# UMR2_CS01_r2_TPL.net
KiCad netlist of a schematic drawn in EAGLE
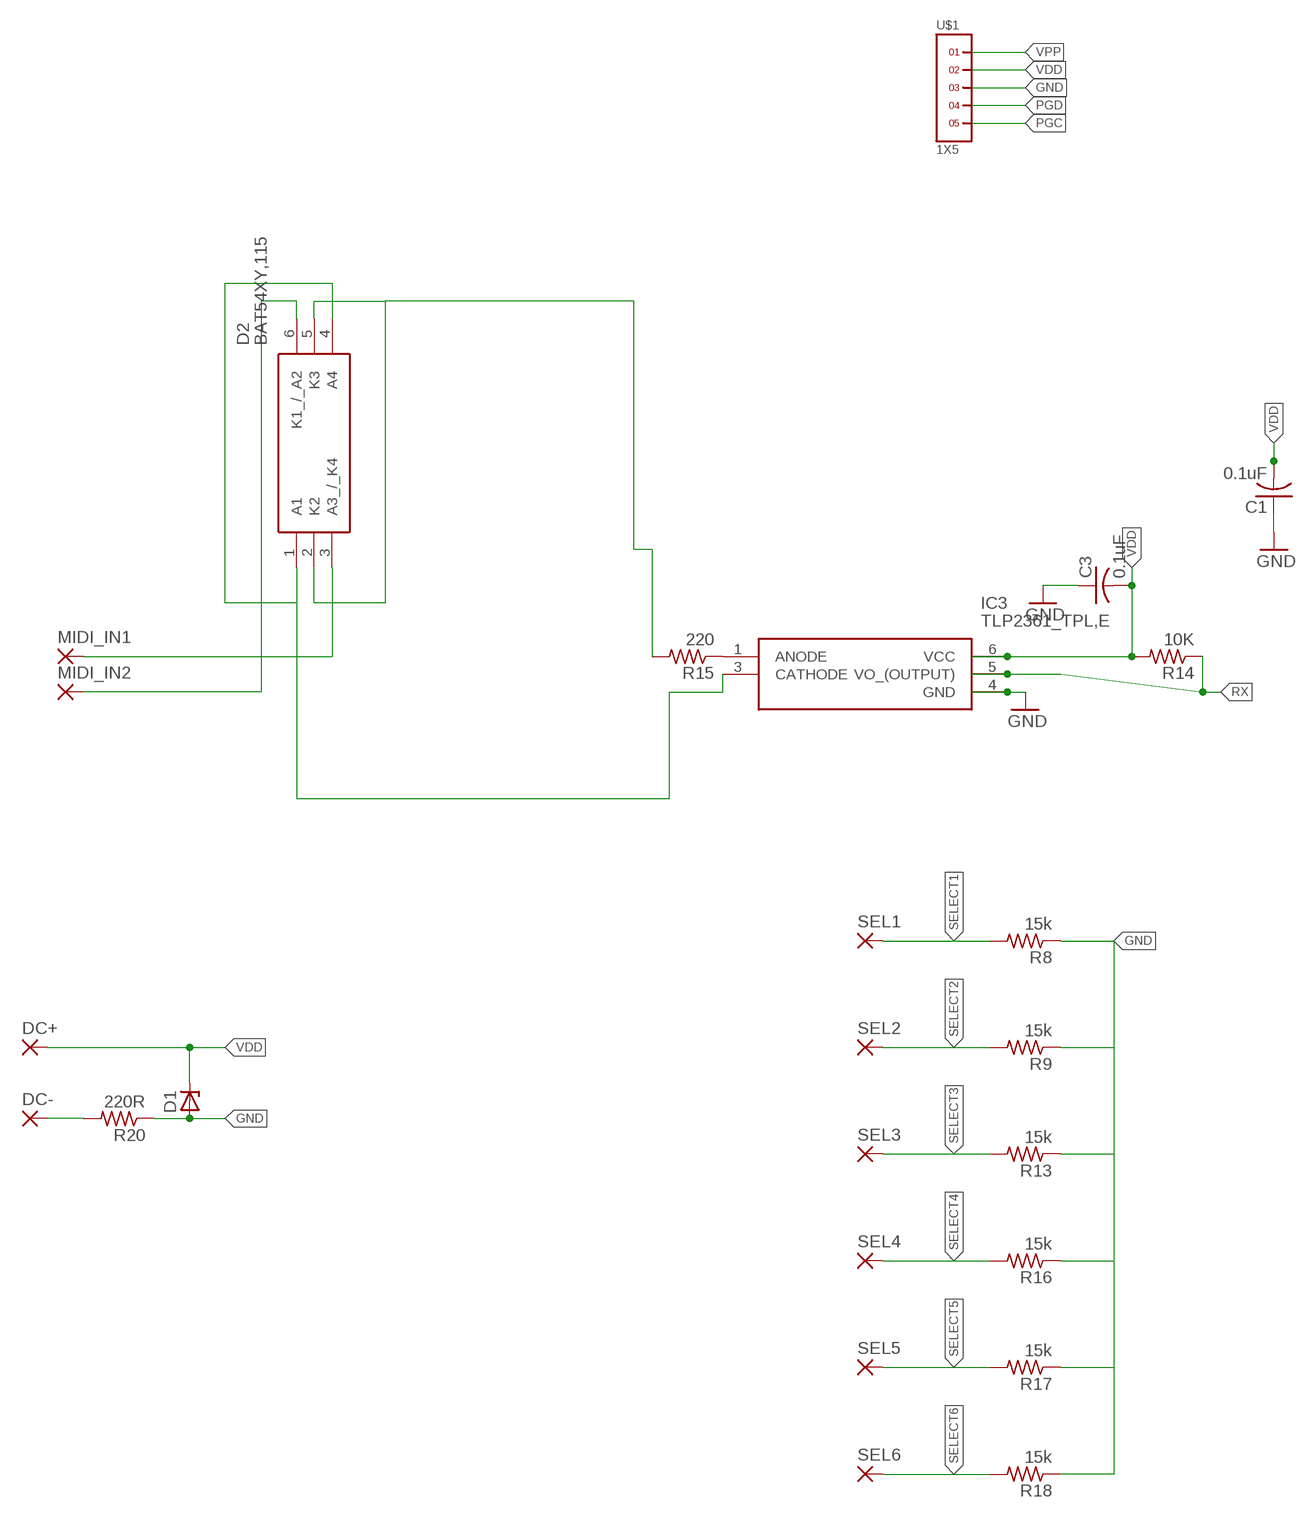
[diagram p0: schematic, sheet 1, part 1 of 2]
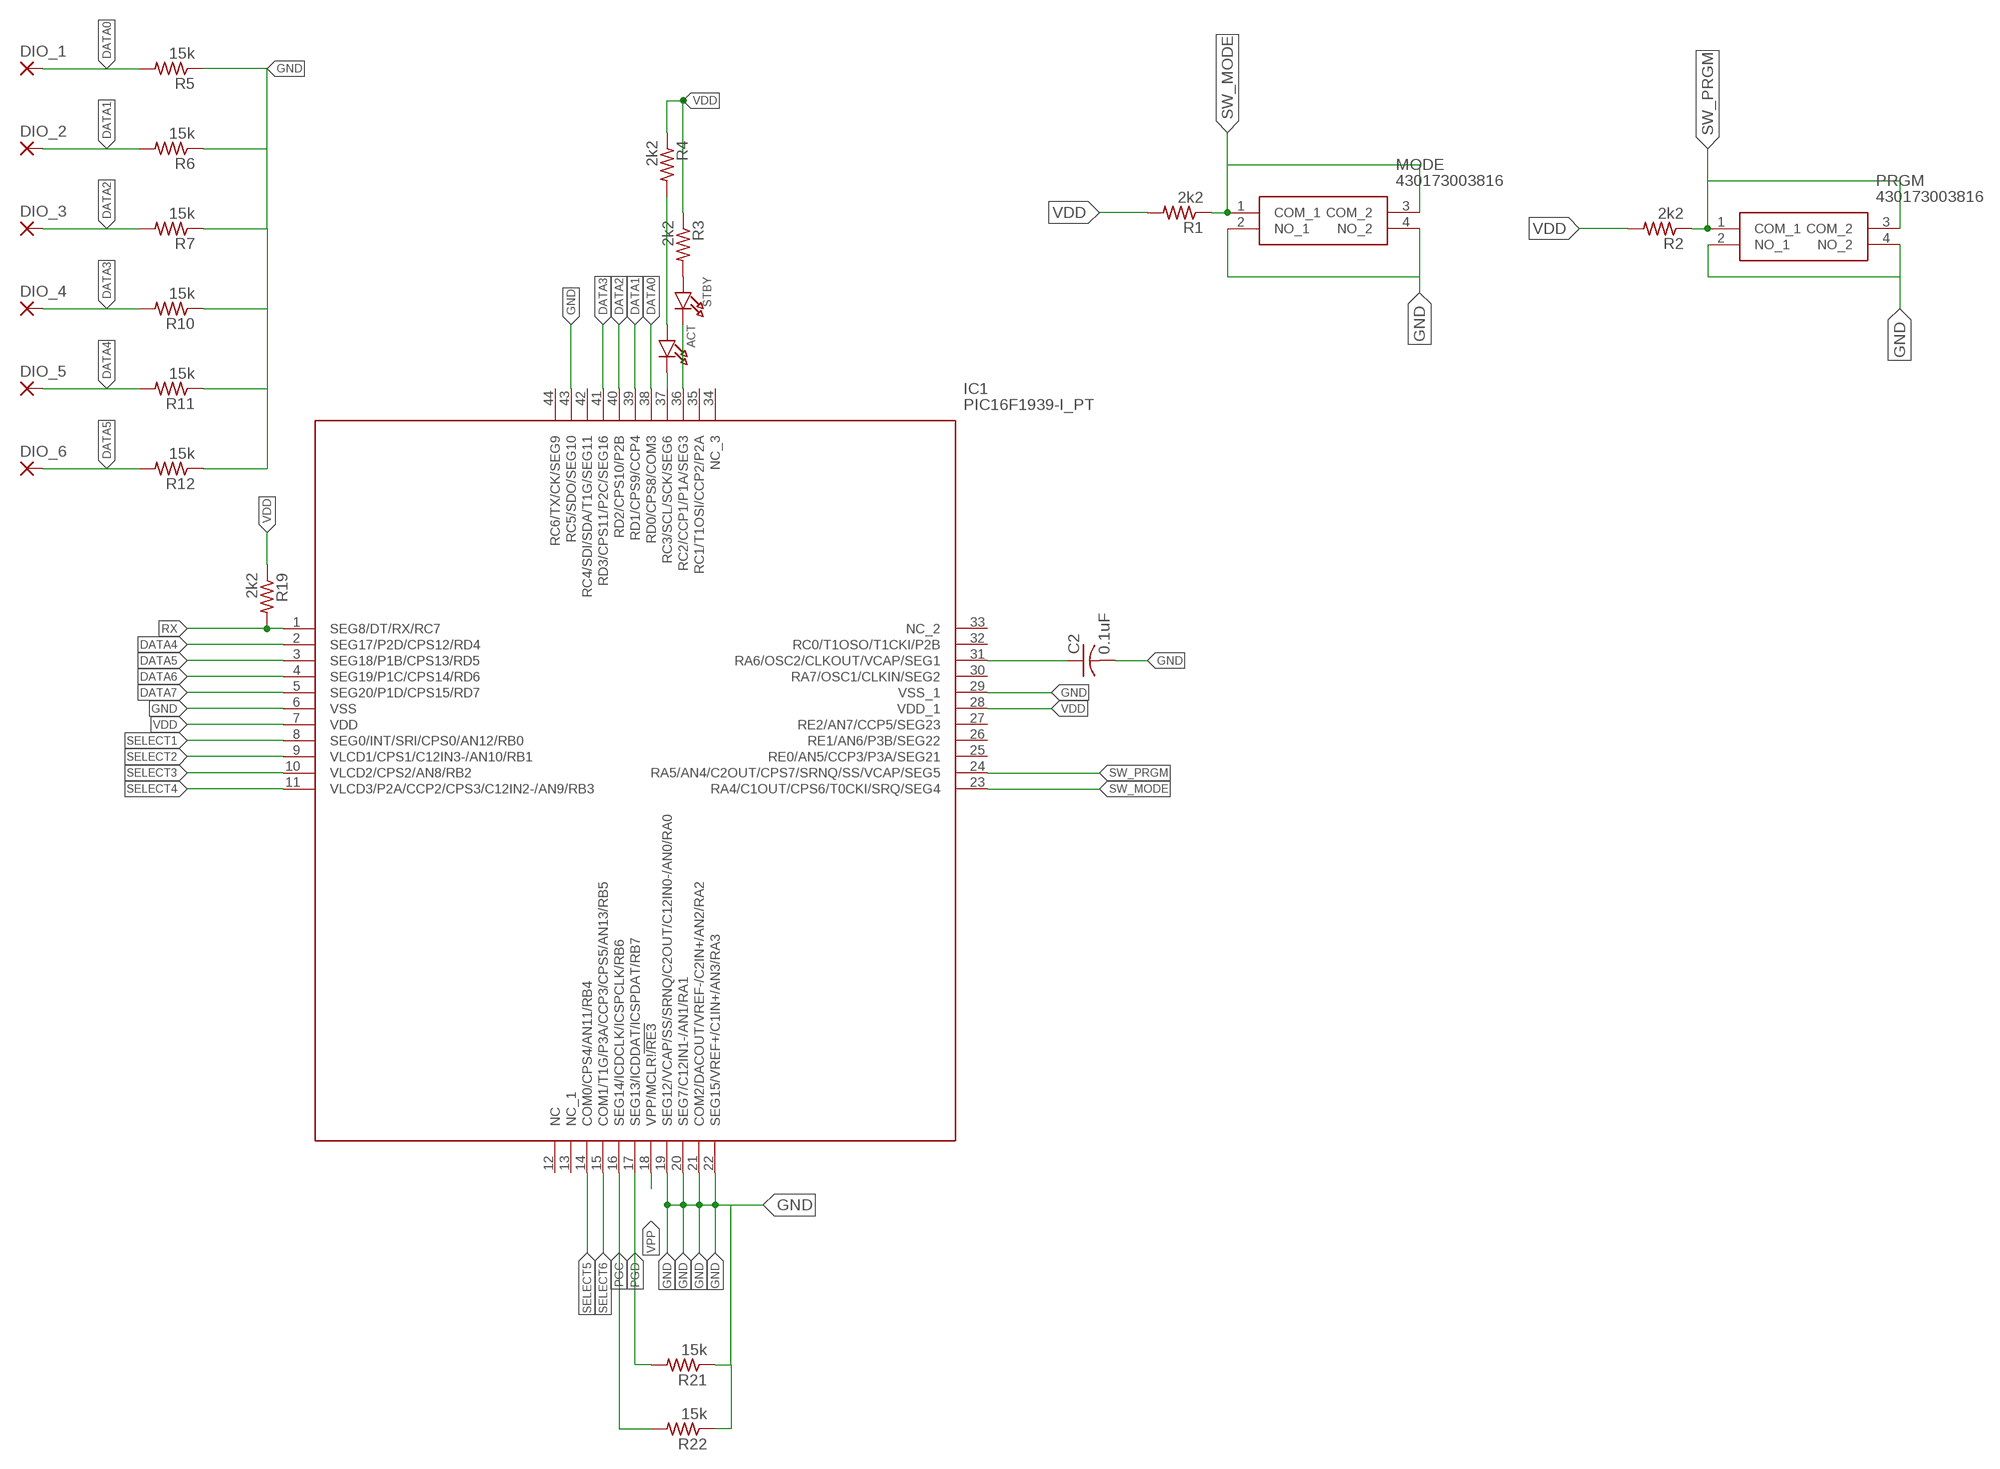
[diagram p1: schematic, sheet 1, part 2 of 2]

(export (version "E")
  (design (tool "Eeschema 10.0.6"))
  (components
    (comp (ref "ACT")
      (value "LED0603_NOOUTLINE")
      (footprint "eagle-import:CHIPLED_0603_NOOUTLINE")
      (libsource (lib "eagle-import") (part "LED0603_NOOUTLINE"))
    )
    (comp (ref "C1")
      (value "0.1uF")
      (footprint "eagle-import:RCL_C0603")
      (libsource (lib "eagle-import") (part "RCL_C-USC0603"))
    )
    (comp (ref "C2")
      (value "0.1uF")
      (footprint "eagle-import:RCL_C0603")
      (libsource (lib "eagle-import") (part "RCL_C-USC0603"))
    )
    (comp (ref "C3")
      (value "0.1uF")
      (footprint "eagle-import:RCL_C0603")
      (libsource (lib "eagle-import") (part "RCL_C-USC0603"))
    )
    (comp (ref "D1")
      (value "ZENER_DIODESOD123")
      (footprint "eagle-import:SOD123")
      (libsource (lib "eagle-import") (part "ZENER_DIODESOD123"))
    )
    (comp (ref "D2")
      (value "BAT54XY,115")
      (footprint "eagle-import:SOT65P210X110-6N")
      (fields (field (name "MOUSER_PART_NUMBER") "771-BAT54XY-T/R"))
      (libsource (lib "eagle-import") (part "BAT54XY,115"))
    )
    (comp (ref "DC+")
      (value "SMD2")
      (footprint "eagle-import:SMD1,27-2,54")
      (libsource (lib "eagle-import") (part "SMD2"))
    )
    (comp (ref "DC-")
      (value "SMD2")
      (footprint "eagle-import:SMD1,27-2,54")
      (libsource (lib "eagle-import") (part "SMD2"))
    )
    (comp (ref "DIO_1")
      (value "SMD2")
      (footprint "eagle-import:SMD1,27-2,54")
      (libsource (lib "eagle-import") (part "SMD2"))
    )
    (comp (ref "DIO_2")
      (value "SMD2")
      (footprint "eagle-import:SMD1,27-2,54")
      (libsource (lib "eagle-import") (part "SMD2"))
    )
    (comp (ref "DIO_3")
      (value "SMD2")
      (footprint "eagle-import:SMD1,27-2,54")
      (libsource (lib "eagle-import") (part "SMD2"))
    )
    (comp (ref "DIO_4")
      (value "SMD2")
      (footprint "eagle-import:SMD1,27-2,54")
      (libsource (lib "eagle-import") (part "SMD2"))
    )
    (comp (ref "DIO_5")
      (value "SMD2")
      (footprint "eagle-import:SMD1,27-2,54")
      (libsource (lib "eagle-import") (part "SMD2"))
    )
    (comp (ref "DIO_6")
      (value "SMD2")
      (footprint "eagle-import:SMD1,27-2,54")
      (libsource (lib "eagle-import") (part "SMD2"))
    )
    (comp (ref "IC1")
      (value "PIC16F1939-I_PT")
      (footprint "eagle-import:QFP80P1200X1200X120-44N")
      (fields
        (field (name "MANUFACTURER_PART_NUMBER") "PIC16F1939-I/PT")
        (field (name "MOUSER_PART_NUMBER") "579-PIC16F1939-I/PT")
      )
      (libsource (lib "eagle-import") (part "PIC16F1939-I_PT"))
    )
    (comp (ref "IC3")
      (value "TLP2361_TPL,E")
      (footprint "eagle-import:11-4L1S(5-PIN-SOIC)")
      (fields
        (field (name "MANUFACTURER_PART_NUMBER") "TLP2361(TPL,E")
        (field (name "MOUSER_PART_NUMBER") "757-TLP2361(TPLE")
      )
      (libsource (lib "eagle-import") (part "TLP2361_TPL,E"))
    )
    (comp (ref "MIDI_IN1")
      (value "SMD2")
      (footprint "eagle-import:SMD1,27-2,54")
      (libsource (lib "eagle-import") (part "SMD2"))
    )
    (comp (ref "MIDI_IN2")
      (value "SMD2")
      (footprint "eagle-import:SMD1,27-2,54")
      (libsource (lib "eagle-import") (part "SMD2"))
    )
    (comp (ref "MODE")
      (value "430173003816")
      (footprint "eagle-import:430173003816")
      (fields (field (name "MOUSER_PART_NUMBER") "710-430173003816"))
      (libsource (lib "eagle-import") (part "430173003816"))
    )
    (comp (ref "PRGM")
      (value "430173003816")
      (footprint "eagle-import:430173003816")
      (fields (field (name "MOUSER_PART_NUMBER") "710-430173003816"))
      (libsource (lib "eagle-import") (part "430173003816"))
    )
    (comp (ref "R1")
      (value "2k2")
      (footprint "eagle-import:RCL_R0603")
      (libsource (lib "eagle-import") (part "RCL_R-US_R0603"))
    )
    (comp (ref "R2")
      (value "2k2")
      (footprint "eagle-import:RCL_R0603")
      (libsource (lib "eagle-import") (part "RCL_R-US_R0603"))
    )
    (comp (ref "R3")
      (value "2k2")
      (footprint "eagle-import:RCL_R0603")
      (libsource (lib "eagle-import") (part "RCL_R-US_R0603"))
    )
    (comp (ref "R4")
      (value "2k2")
      (footprint "eagle-import:RCL_R0603")
      (libsource (lib "eagle-import") (part "RCL_R-US_R0603"))
    )
    (comp (ref "R5")
      (value "15k")
      (footprint "eagle-import:RCL_R0603")
      (libsource (lib "eagle-import") (part "RCL_R-US_R0603"))
    )
    (comp (ref "R6")
      (value "15k")
      (footprint "eagle-import:RCL_R0603")
      (libsource (lib "eagle-import") (part "RCL_R-US_R0603"))
    )
    (comp (ref "R7")
      (value "15k")
      (footprint "eagle-import:RCL_R0603")
      (libsource (lib "eagle-import") (part "RCL_R-US_R0603"))
    )
    (comp (ref "R8")
      (value "15k")
      (footprint "eagle-import:RCL_R0603")
      (libsource (lib "eagle-import") (part "RCL_R-US_R0603"))
    )
    (comp (ref "R9")
      (value "15k")
      (footprint "eagle-import:RCL_R0603")
      (libsource (lib "eagle-import") (part "RCL_R-US_R0603"))
    )
    (comp (ref "R10")
      (value "15k")
      (footprint "eagle-import:RCL_R0603")
      (libsource (lib "eagle-import") (part "RCL_R-US_R0603"))
    )
    (comp (ref "R11")
      (value "15k")
      (footprint "eagle-import:RCL_R0603")
      (libsource (lib "eagle-import") (part "RCL_R-US_R0603"))
    )
    (comp (ref "R12")
      (value "15k")
      (footprint "eagle-import:RCL_R0603")
      (libsource (lib "eagle-import") (part "RCL_R-US_R0603"))
    )
    (comp (ref "R13")
      (value "15k")
      (footprint "eagle-import:RCL_R0603")
      (libsource (lib "eagle-import") (part "RCL_R-US_R0603"))
    )
    (comp (ref "R14")
      (value "10K")
      (footprint "eagle-import:RCL_R0603")
      (libsource (lib "eagle-import") (part "RCL_R-US_R0603"))
    )
    (comp (ref "R15")
      (value "220")
      (footprint "eagle-import:RCL_R0603")
      (libsource (lib "eagle-import") (part "RCL_R-US_R0603"))
    )
    (comp (ref "R16")
      (value "15k")
      (footprint "eagle-import:RCL_R0603")
      (libsource (lib "eagle-import") (part "RCL_R-US_R0603"))
    )
    (comp (ref "R17")
      (value "15k")
      (footprint "eagle-import:RCL_R0603")
      (libsource (lib "eagle-import") (part "RCL_R-US_R0603"))
    )
    (comp (ref "R18")
      (value "15k")
      (footprint "eagle-import:RCL_R0603")
      (libsource (lib "eagle-import") (part "RCL_R-US_R0603"))
    )
    (comp (ref "R19")
      (value "2k2")
      (footprint "eagle-import:RCL_R0603")
      (libsource (lib "eagle-import") (part "RCL_R-US_R0603"))
    )
    (comp (ref "R20")
      (value "220R")
      (footprint "eagle-import:RCL_R0603")
      (libsource (lib "eagle-import") (part "RCL_R-US_R0603"))
    )
    (comp (ref "R21")
      (value "15k")
      (footprint "eagle-import:RCL_R0603")
      (libsource (lib "eagle-import") (part "RCL_R-US_R0603"))
    )
    (comp (ref "R22")
      (value "15k")
      (footprint "eagle-import:RCL_R0603")
      (libsource (lib "eagle-import") (part "RCL_R-US_R0603"))
    )
    (comp (ref "SEL1")
      (value "SMD2")
      (footprint "eagle-import:SMD1,27-2,54")
      (libsource (lib "eagle-import") (part "SMD2"))
    )
    (comp (ref "SEL2")
      (value "SMD2")
      (footprint "eagle-import:SMD1,27-2,54")
      (libsource (lib "eagle-import") (part "SMD2"))
    )
    (comp (ref "SEL3")
      (value "SMD2")
      (footprint "eagle-import:SMD1,27-2,54")
      (libsource (lib "eagle-import") (part "SMD2"))
    )
    (comp (ref "SEL4")
      (value "SMD2")
      (footprint "eagle-import:SMD1,27-2,54")
      (libsource (lib "eagle-import") (part "SMD2"))
    )
    (comp (ref "SEL5")
      (value "SMD2")
      (footprint "eagle-import:SMD1,27-2,54")
      (libsource (lib "eagle-import") (part "SMD2"))
    )
    (comp (ref "SEL6")
      (value "SMD2")
      (footprint "eagle-import:SMD1,27-2,54")
      (libsource (lib "eagle-import") (part "SMD2"))
    )
    (comp (ref "STBY")
      (value "LED0603_NOOUTLINE")
      (footprint "eagle-import:CHIPLED_0603_NOOUTLINE")
      (libsource (lib "eagle-import") (part "LED0603_NOOUTLINE"))
    )
    (comp (ref "U$1")
      (value "1X5")
      (footprint "eagle-import:1X5")
      (libsource (lib "eagle-import") (part "1X5"))
    )
  )
  (nets
    (net (code "1") (name "DATA0") (class "Default")
      (node (ref "DIO_1") (pin "1") (pinfunction "P_1") (pintype "passive"))
      (node (ref "IC1") (pin "38") (pinfunction "RD0/CPS8/COM3_38") (pintype "bidirectional"))
      (node (ref "R5") (pin "2") (pinfunction "2_2") (pintype "passive"))
    )
    (net (code "2") (name "DATA1") (class "Default")
      (node (ref "DIO_2") (pin "1") (pinfunction "P_1") (pintype "passive"))
      (node (ref "IC1") (pin "39") (pinfunction "RD1/CPS9/CCP4_39") (pintype "bidirectional"))
      (node (ref "R6") (pin "2") (pinfunction "2_2") (pintype "passive"))
    )
    (net (code "3") (name "DATA2") (class "Default")
      (node (ref "DIO_3") (pin "1") (pinfunction "P_1") (pintype "passive"))
      (node (ref "IC1") (pin "40") (pinfunction "RD2/CPS10/P2B_40") (pintype "bidirectional"))
      (node (ref "R7") (pin "2") (pinfunction "2_2") (pintype "passive"))
    )
    (net (code "4") (name "DATA3") (class "Default")
      (node (ref "DIO_4") (pin "1") (pinfunction "P_1") (pintype "passive"))
      (node (ref "IC1") (pin "41") (pinfunction "RD3/CPS11/P2C/SEG16_41") (pintype "bidirectional"))
      (node (ref "R10") (pin "2") (pinfunction "2_2") (pintype "passive"))
    )
    (net (code "5") (name "DATA4") (class "Default")
      (node (ref "DIO_5") (pin "1") (pinfunction "P_1") (pintype "passive"))
      (node (ref "IC1") (pin "2") (pinfunction "SEG17/P2D/CPS12/RD4_2") (pintype "bidirectional"))
      (node (ref "R11") (pin "2") (pinfunction "2_2") (pintype "passive"))
    )
    (net (code "6") (name "DATA5") (class "Default")
      (node (ref "DIO_6") (pin "1") (pinfunction "P_1") (pintype "passive"))
      (node (ref "IC1") (pin "3") (pinfunction "SEG18/P1B/CPS13/RD5_3") (pintype "bidirectional"))
      (node (ref "R12") (pin "2") (pinfunction "2_2") (pintype "passive"))
    )
    (net (code "7") (name "DATA6") (class "Default")
      (node (ref "IC1") (pin "4") (pinfunction "SEG19/P1C/CPS14/RD6_4") (pintype "bidirectional"))
    )
    (net (code "8") (name "DATA7") (class "Default")
      (node (ref "IC1") (pin "5") (pinfunction "SEG20/P1D/CPS15/RD7_5") (pintype "bidirectional"))
    )
    (net (code "9") (name "GND") (class "Default")
      (node (ref "C1") (pin "1") (pinfunction "1_1") (pintype "passive"))
      (node (ref "C2") (pin "2") (pinfunction "2_2") (pintype "passive"))
      (node (ref "C3") (pin "1") (pinfunction "1_1") (pintype "passive"))
      (node (ref "D1") (pin "ANODE") (pinfunction "ANODE_ANODE") (pintype "passive"))
      (node (ref "IC1") (pin "19") (pinfunction "SEG12/VCAP/SS/SRNQ/C2OUT/C12IN0-/AN0/RA0_19") (pintype "output"))
      (node (ref "IC1") (pin "20") (pinfunction "SEG7/C12IN1-/AN1/RA1_20") (pintype "input"))
      (node (ref "IC1") (pin "21") (pinfunction "COM2/DACOUT/VREF-/C2IN+/AN2/RA2_21") (pintype "output"))
      (node (ref "IC1") (pin "22") (pinfunction "SEG15/VREF+/C1IN+/AN3/RA3_22") (pintype "input"))
      (node (ref "IC1") (pin "29") (pinfunction "VSS_1_29") (pintype "power_in"))
      (node (ref "IC1") (pin "43") (pinfunction "RC5/SDO/SEG10_43") (pintype "bidirectional"))
      (node (ref "IC1") (pin "6") (pinfunction "VSS_6") (pintype "power_in"))
      (node (ref "IC3") (pin "4") (pinfunction "GND_4") (pintype "bidirectional"))
      (node (ref "MODE") (pin "2") (pinfunction "NO_1_2") (pintype "bidirectional"))
      (node (ref "MODE") (pin "4") (pinfunction "NO_2_4") (pintype "bidirectional"))
      (node (ref "PRGM") (pin "2") (pinfunction "NO_1_2") (pintype "bidirectional"))
      (node (ref "PRGM") (pin "4") (pinfunction "NO_2_4") (pintype "bidirectional"))
      (node (ref "R10") (pin "1") (pinfunction "1_1") (pintype "passive"))
      (node (ref "R11") (pin "1") (pinfunction "1_1") (pintype "passive"))
      (node (ref "R12") (pin "1") (pinfunction "1_1") (pintype "passive"))
      (node (ref "R13") (pin "1") (pinfunction "1_1") (pintype "passive"))
      (node (ref "R16") (pin "1") (pinfunction "1_1") (pintype "passive"))
      (node (ref "R17") (pin "1") (pinfunction "1_1") (pintype "passive"))
      (node (ref "R18") (pin "1") (pinfunction "1_1") (pintype "passive"))
      (node (ref "R20") (pin "1") (pinfunction "1_1") (pintype "passive"))
      (node (ref "R21") (pin "1") (pinfunction "1_1") (pintype "passive"))
      (node (ref "R22") (pin "1") (pinfunction "1_1") (pintype "passive"))
      (node (ref "R5") (pin "1") (pinfunction "1_1") (pintype "passive"))
      (node (ref "R6") (pin "1") (pinfunction "1_1") (pintype "passive"))
      (node (ref "R7") (pin "1") (pinfunction "1_1") (pintype "passive"))
      (node (ref "R8") (pin "1") (pinfunction "1_1") (pintype "passive"))
      (node (ref "R9") (pin "1") (pinfunction "1_1") (pintype "passive"))
      (node (ref "U$1") (pin "3") (pinfunction "3_3") (pintype "bidirectional"))
    )
    (net (code "10") (name "Net-(ACT-PadA)") (class "Default")
      (node (ref "ACT") (pin "A") (pinfunction "A_A") (pintype "passive"))
      (node (ref "R4") (pin "2") (pinfunction "2_2") (pintype "passive"))
    )
    (net (code "11") (name "Net-(D2-A1)") (class "Default")
      (node (ref "D2") (pin "1") (pinfunction "A1_1") (pintype "bidirectional"))
      (node (ref "D2") (pin "4") (pinfunction "A4_4") (pintype "bidirectional"))
      (node (ref "IC3") (pin "3") (pinfunction "CATHODE_3") (pintype "bidirectional"))
    )
    (net (code "12") (name "Net-(D2-A3_{slash}_K4)") (class "Default")
      (node (ref "D2") (pin "3") (pinfunction "A3_/_K4_3") (pintype "bidirectional"))
      (node (ref "MIDI_IN1") (pin "1") (pinfunction "P_1") (pintype "passive"))
    )
    (net (code "13") (name "Net-(D2-K1_{slash}_A2)") (class "Default")
      (node (ref "D2") (pin "6") (pinfunction "K1_/_A2_6") (pintype "bidirectional"))
      (node (ref "MIDI_IN2") (pin "1") (pinfunction "P_1") (pintype "passive"))
    )
    (net (code "14") (name "Net-(D2-K2)") (class "Default")
      (node (ref "D2") (pin "2") (pinfunction "K2_2") (pintype "bidirectional"))
      (node (ref "D2") (pin "5") (pinfunction "K3_5") (pintype "bidirectional"))
      (node (ref "R15") (pin "2") (pinfunction "2_2") (pintype "passive"))
    )
    (net (code "15") (name "Net-(DC--P)") (class "Default")
      (node (ref "DC-") (pin "1") (pinfunction "P_1") (pintype "passive"))
      (node (ref "R20") (pin "2") (pinfunction "2_2") (pintype "passive"))
    )
    (net (code "16") (name "Net-(IC1-RA6{slash}OSC2{slash}CLKOUT{slash}VCAP{slash}SEG1)") (class "Default")
      (node (ref "C2") (pin "1") (pinfunction "1_1") (pintype "passive"))
      (node (ref "IC1") (pin "31") (pinfunction "RA6/OSC2/CLKOUT/VCAP/SEG1_31") (pintype "output"))
    )
    (net (code "17") (name "Net-(IC1-RC2{slash}CCP1{slash}P1A{slash}SEG3)") (class "Default")
      (node (ref "IC1") (pin "36") (pinfunction "RC2/CCP1/P1A/SEG3_36") (pintype "bidirectional"))
      (node (ref "STBY") (pin "C") (pinfunction "C_C") (pintype "passive"))
    )
    (net (code "18") (name "Net-(IC1-RC3{slash}SCL{slash}SCK{slash}SEG6)") (class "Default")
      (node (ref "ACT") (pin "C") (pinfunction "C_C") (pintype "passive"))
      (node (ref "IC1") (pin "37") (pinfunction "RC3/SCL/SCK/SEG6_37") (pintype "bidirectional"))
    )
    (net (code "19") (name "Net-(IC3-ANODE)") (class "Default")
      (node (ref "IC3") (pin "1") (pinfunction "ANODE_1") (pintype "bidirectional"))
      (node (ref "R15") (pin "1") (pinfunction "1_1") (pintype "passive"))
    )
    (net (code "20") (name "Net-(R3-Pad2)") (class "Default")
      (node (ref "R3") (pin "2") (pinfunction "2_2") (pintype "passive"))
      (node (ref "STBY") (pin "A") (pinfunction "A_A") (pintype "passive"))
    )
    (net (code "21") (name "PGC") (class "Default")
      (node (ref "IC1") (pin "16") (pinfunction "SEG14/ICDCLK/ICSPCLK/RB6_16") (pintype "input"))
      (node (ref "R22") (pin "2") (pinfunction "2_2") (pintype "passive"))
      (node (ref "U$1") (pin "5") (pinfunction "5_5") (pintype "bidirectional"))
    )
    (net (code "22") (name "PGD") (class "Default")
      (node (ref "IC1") (pin "17") (pinfunction "SEG13/ICDDAT/ICSPDAT/RB7_17") (pintype "input"))
      (node (ref "R21") (pin "2") (pinfunction "2_2") (pintype "passive"))
      (node (ref "U$1") (pin "4") (pinfunction "4_4") (pintype "bidirectional"))
    )
    (net (code "23") (name "RX") (class "Default")
      (node (ref "IC1") (pin "1") (pinfunction "SEG8/DT/RX/RC7_1") (pintype "bidirectional"))
      (node (ref "IC3") (pin "5") (pinfunction "VO_(OUTPUT)_5") (pintype "bidirectional"))
      (node (ref "R14") (pin "1") (pinfunction "1_1") (pintype "passive"))
      (node (ref "R19") (pin "2") (pinfunction "2_2") (pintype "passive"))
    )
    (net (code "24") (name "SELECT1") (class "Default")
      (node (ref "IC1") (pin "8") (pinfunction "SEG0/INT/SRI/CPS0/AN12/RB0_8") (pintype "input"))
      (node (ref "R8") (pin "2") (pinfunction "2_2") (pintype "passive"))
      (node (ref "SEL1") (pin "1") (pinfunction "P_1") (pintype "passive"))
    )
    (net (code "25") (name "SELECT2") (class "Default")
      (node (ref "IC1") (pin "9") (pinfunction "VLCD1/CPS1/C12IN3-/AN10/RB1_9") (pintype "input"))
      (node (ref "R9") (pin "2") (pinfunction "2_2") (pintype "passive"))
      (node (ref "SEL2") (pin "1") (pinfunction "P_1") (pintype "passive"))
    )
    (net (code "26") (name "SELECT3") (class "Default")
      (node (ref "IC1") (pin "10") (pinfunction "VLCD2/CPS2/AN8/RB2_10") (pintype "bidirectional"))
      (node (ref "R13") (pin "2") (pinfunction "2_2") (pintype "passive"))
      (node (ref "SEL3") (pin "1") (pinfunction "P_1") (pintype "passive"))
    )
    (net (code "27") (name "SELECT4") (class "Default")
      (node (ref "IC1") (pin "11") (pinfunction "VLCD3/P2A/CCP2/CPS3/C12IN2-/AN9/RB3_11") (pintype "input"))
      (node (ref "R16") (pin "2") (pinfunction "2_2") (pintype "passive"))
      (node (ref "SEL4") (pin "1") (pinfunction "P_1") (pintype "passive"))
    )
    (net (code "28") (name "SELECT5") (class "Default")
      (node (ref "IC1") (pin "14") (pinfunction "COM0/CPS4/AN11/RB4_14") (pintype "bidirectional"))
      (node (ref "R17") (pin "2") (pinfunction "2_2") (pintype "passive"))
      (node (ref "SEL5") (pin "1") (pinfunction "P_1") (pintype "passive"))
    )
    (net (code "29") (name "SELECT6") (class "Default")
      (node (ref "IC1") (pin "15") (pinfunction "COM1/T1G/P3A/CCP3/CPS5/AN13/RB5_15") (pintype "bidirectional"))
      (node (ref "R18") (pin "2") (pinfunction "2_2") (pintype "passive"))
      (node (ref "SEL6") (pin "1") (pinfunction "P_1") (pintype "passive"))
    )
    (net (code "30") (name "SW_MODE") (class "Default")
      (node (ref "IC1") (pin "23") (pinfunction "RA4/C1OUT/CPS6/T0CKI/SRQ/SEG4_23") (pintype "output"))
      (node (ref "MODE") (pin "1") (pinfunction "COM_1_1") (pintype "bidirectional"))
      (node (ref "MODE") (pin "3") (pinfunction "COM_2_3") (pintype "bidirectional"))
      (node (ref "R1") (pin "1") (pinfunction "1_1") (pintype "passive"))
    )
    (net (code "31") (name "SW_PRGM") (class "Default")
      (node (ref "IC1") (pin "24") (pinfunction "RA5/AN4/C2OUT/CPS7/SRNQ/SS/VCAP/SEG5_24") (pintype "output"))
      (node (ref "PRGM") (pin "1") (pinfunction "COM_1_1") (pintype "bidirectional"))
      (node (ref "PRGM") (pin "3") (pinfunction "COM_2_3") (pintype "bidirectional"))
      (node (ref "R2") (pin "1") (pinfunction "1_1") (pintype "passive"))
    )
    (net (code "32") (name "VDD") (class "Default")
      (node (ref "C1") (pin "2") (pinfunction "2_2") (pintype "passive"))
      (node (ref "C3") (pin "2") (pinfunction "2_2") (pintype "passive"))
      (node (ref "D1") (pin "CATHODE") (pinfunction "CATHODE_CATHODE") (pintype "passive"))
      (node (ref "DC+") (pin "1") (pinfunction "P_1") (pintype "passive"))
      (node (ref "IC1") (pin "28") (pinfunction "VDD_1_28") (pintype "power_in"))
      (node (ref "IC1") (pin "7") (pinfunction "VDD_7") (pintype "power_in"))
      (node (ref "IC3") (pin "6") (pinfunction "VCC_6") (pintype "bidirectional"))
      (node (ref "R1") (pin "2") (pinfunction "2_2") (pintype "passive"))
      (node (ref "R14") (pin "2") (pinfunction "2_2") (pintype "passive"))
      (node (ref "R19") (pin "1") (pinfunction "1_1") (pintype "passive"))
      (node (ref "R2") (pin "2") (pinfunction "2_2") (pintype "passive"))
      (node (ref "R3") (pin "1") (pinfunction "1_1") (pintype "passive"))
      (node (ref "R4") (pin "1") (pinfunction "1_1") (pintype "passive"))
      (node (ref "U$1") (pin "2") (pinfunction "2_2") (pintype "bidirectional"))
    )
    (net (code "33") (name "VPP") (class "Default")
      (node (ref "IC1") (pin "18") (pinfunction "VPP/MCLR~/RE3_18") (pintype "bidirectional"))
      (node (ref "U$1") (pin "1") (pinfunction "1_1") (pintype "bidirectional"))
    )
    (net (code "34") (name "unconnected-(IC1-NC-Pad12)") (class "Default")
      (node (ref "IC1") (pin "12") (pinfunction "NC_12") (pintype "no_connect"))
    )
    (net (code "35") (name "unconnected-(IC1-NC_1-Pad13)") (class "Default")
      (node (ref "IC1") (pin "13") (pinfunction "NC_1_13") (pintype "bidirectional"))
    )
    (net (code "36") (name "unconnected-(IC1-NC_2-Pad33)") (class "Default")
      (node (ref "IC1") (pin "33") (pinfunction "NC_2_33") (pintype "bidirectional"))
    )
    (net (code "37") (name "unconnected-(IC1-NC_3-Pad34)") (class "Default")
      (node (ref "IC1") (pin "34") (pinfunction "NC_3_34") (pintype "bidirectional"))
    )
    (net (code "38") (name "unconnected-(IC1-RA7{slash}OSC1{slash}CLKIN{slash}SEG2-Pad30)") (class "Default")
      (node (ref "IC1") (pin "30") (pinfunction "RA7/OSC1/CLKIN/SEG2_30") (pintype "input"))
    )
    (net (code "39") (name "unconnected-(IC1-RC0{slash}T1OSO{slash}T1CKI{slash}P2B-Pad32)") (class "Default")
      (node (ref "IC1") (pin "32") (pinfunction "RC0/T1OSO/T1CKI/P2B_32") (pintype "bidirectional"))
    )
    (net (code "40") (name "unconnected-(IC1-RC1{slash}T1OSI{slash}CCP2{slash}P2A-Pad35)") (class "Default")
      (node (ref "IC1") (pin "35") (pinfunction "RC1/T1OSI/CCP2/P2A_35") (pintype "bidirectional"))
    )
    (net (code "41") (name "unconnected-(IC1-RC4{slash}SDI{slash}SDA{slash}T1G{slash}SEG11-Pad42)") (class "Default")
      (node (ref "IC1") (pin "42") (pinfunction "RC4/SDI/SDA/T1G/SEG11_42") (pintype "bidirectional"))
    )
    (net (code "42") (name "unconnected-(IC1-RC6{slash}TX{slash}CK{slash}SEG9-Pad44)") (class "Default")
      (node (ref "IC1") (pin "44") (pinfunction "RC6/TX/CK/SEG9_44") (pintype "bidirectional"))
    )
    (net (code "43") (name "unconnected-(IC1-RE0{slash}AN5{slash}CCP3{slash}P3A{slash}SEG21-Pad25)") (class "Default")
      (node (ref "IC1") (pin "25") (pinfunction "RE0/AN5/CCP3/P3A/SEG21_25") (pintype "bidirectional"))
    )
    (net (code "44") (name "unconnected-(IC1-RE1{slash}AN6{slash}P3B{slash}SEG22-Pad26)") (class "Default")
      (node (ref "IC1") (pin "26") (pinfunction "RE1/AN6/P3B/SEG22_26") (pintype "bidirectional"))
    )
    (net (code "45") (name "unconnected-(IC1-RE2{slash}AN7{slash}CCP5{slash}SEG23-Pad27)") (class "Default")
      (node (ref "IC1") (pin "27") (pinfunction "RE2/AN7/CCP5/SEG23_27") (pintype "bidirectional"))
    )
  )
)
